# Peripheral.net
KiCad netlist of a schematic drawn in Altium Designer
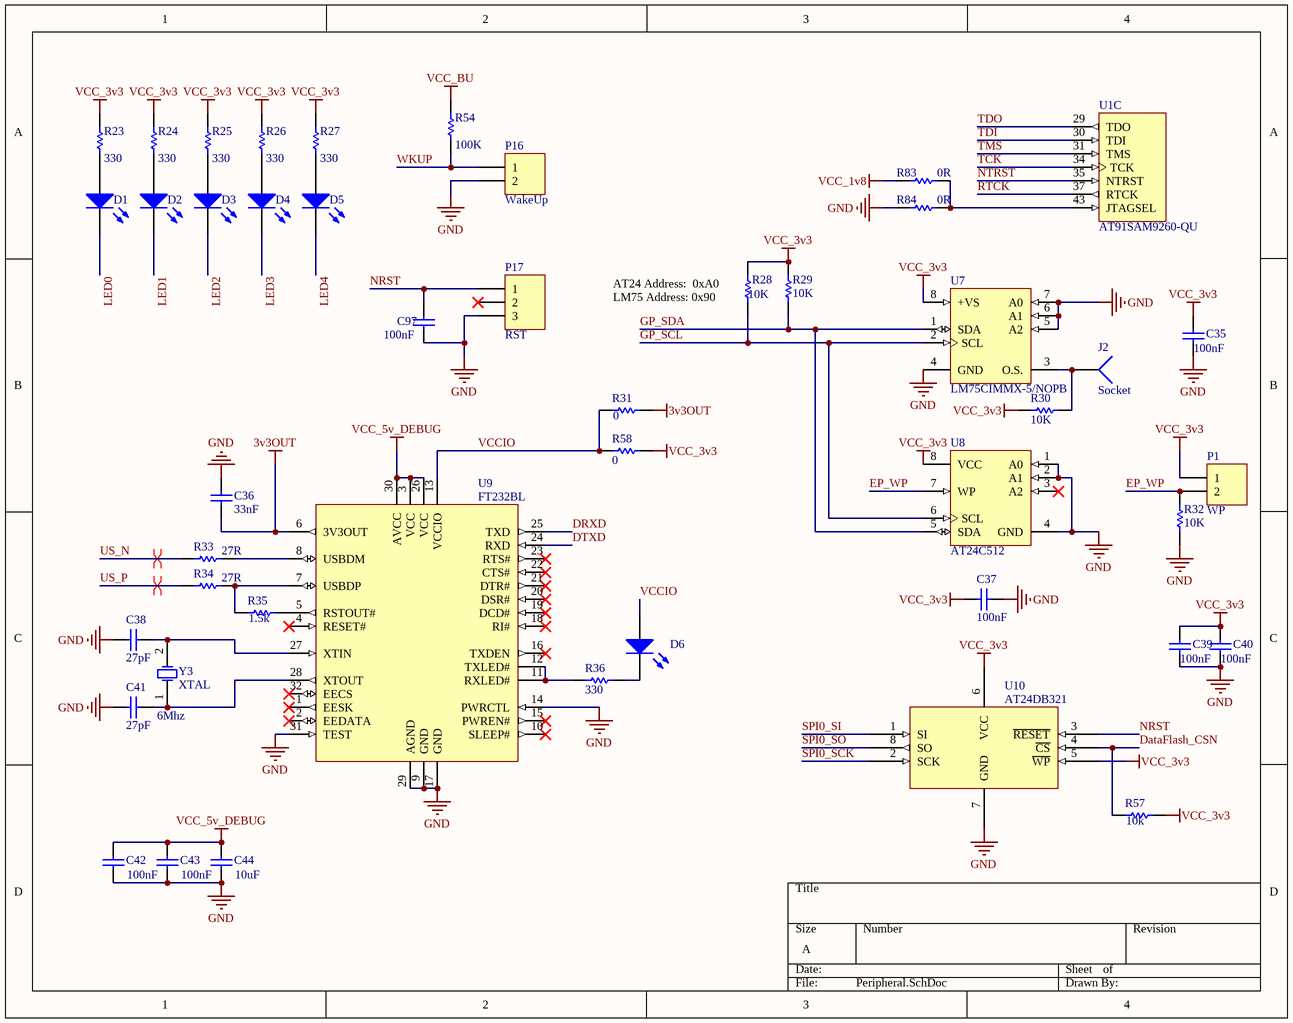
[diagram p0: Peripheral.SchDoc]

(export (version "E")
  (design (tool "Eeschema 10.0.6"))
  (components
    (comp (ref "C35")
      (value "100nF")
      (footprint "C0805")
      (description "Capacitor")
      (fields (field (name "Comment") "Cap") (field (name "PUBLISHER") "Altium Limited"))
      (libsource (lib "Miscellaneous Devices") (part "Cap"))
    )
    (comp (ref "C36")
      (value "33nF")
      (footprint "C0805")
      (description "Capacitor")
      (fields (field (name "Comment") "Cap") (field (name "PUBLISHER") "Altium Limited"))
      (libsource (lib "Miscellaneous Devices") (part "Cap"))
    )
    (comp (ref "C37")
      (value "100nF")
      (footprint "C0805")
      (description "Capacitor")
      (fields (field (name "Comment") "Cap") (field (name "PUBLISHER") "Altium Limited"))
      (libsource (lib "Miscellaneous Devices") (part "Cap"))
    )
    (comp (ref "C38")
      (value "27pF")
      (footprint "C0805")
      (description "Capacitor")
      (fields (field (name "Comment") "Cap") (field (name "PUBLISHER") "Altium Limited"))
      (libsource (lib "Miscellaneous Devices") (part "Cap"))
    )
    (comp (ref "C39")
      (value "100nF")
      (footprint "C0805")
      (description "Capacitor")
      (fields (field (name "Comment") "Cap") (field (name "PUBLISHER") "Altium Limited"))
      (libsource (lib "Miscellaneous Devices") (part "Cap"))
    )
    (comp (ref "C40")
      (value "100nF")
      (footprint "C0805")
      (description "Capacitor")
      (fields (field (name "Comment") "Cap") (field (name "PUBLISHER") "Altium Limited"))
      (libsource (lib "Miscellaneous Devices") (part "Cap"))
    )
    (comp (ref "C41")
      (value "27pF")
      (footprint "C0805")
      (description "Capacitor")
      (fields (field (name "Comment") "Cap") (field (name "PUBLISHER") "Altium Limited"))
      (libsource (lib "Miscellaneous Devices") (part "Cap"))
    )
    (comp (ref "C42")
      (value "100nF")
      (footprint "C0805")
      (description "Capacitor")
      (fields (field (name "Comment") "Cap") (field (name "PUBLISHER") "Altium Limited"))
      (libsource (lib "Miscellaneous Devices") (part "Cap"))
    )
    (comp (ref "C43")
      (value "100nF")
      (footprint "C0805")
      (description "Capacitor")
      (fields (field (name "Comment") "Cap") (field (name "PUBLISHER") "Altium Limited"))
      (libsource (lib "Miscellaneous Devices") (part "Cap"))
    )
    (comp (ref "C44")
      (value "10uF")
      (footprint "C0805")
      (description "Capacitor")
      (fields (field (name "Comment") "Cap") (field (name "PUBLISHER") "Altium Limited"))
      (libsource (lib "Miscellaneous Devices") (part "Cap"))
    )
    (comp (ref "C97")
      (value "100nF")
      (footprint "C0805")
      (description "Capacitor")
      (fields (field (name "Comment") "Cap") (field (name "PUBLISHER") "Altium Limited"))
      (libsource (lib "Miscellaneous Devices") (part "Cap"))
    )
    (comp (ref "D1")
      (value "LED0")
      (footprint "SMD_LED_1206")
      (description "Typical INFRARED GaAs LED")
      (fields (field (name "PUBLISHER") "Altium Limited"))
      (libsource (lib "Miscellaneous Devices") (part "LED0"))
    )
    (comp (ref "D2")
      (value "LED0")
      (footprint "SMD_LED_1206")
      (description "Typical INFRARED GaAs LED")
      (fields (field (name "PUBLISHER") "Altium Limited"))
      (libsource (lib "Miscellaneous Devices") (part "LED0"))
    )
    (comp (ref "D3")
      (value "LED0")
      (footprint "SMD_LED_1206")
      (description "Typical INFRARED GaAs LED")
      (fields (field (name "PUBLISHER") "Altium Limited"))
      (libsource (lib "Miscellaneous Devices") (part "LED0"))
    )
    (comp (ref "D4")
      (value "LED0")
      (footprint "SMD_LED_1206")
      (description "Typical INFRARED GaAs LED")
      (fields (field (name "PUBLISHER") "Altium Limited"))
      (libsource (lib "Miscellaneous Devices") (part "LED0"))
    )
    (comp (ref "D5")
      (value "LED0")
      (footprint "SMD_LED_1206")
      (description "Typical INFRARED GaAs LED")
      (fields (field (name "PUBLISHER") "Altium Limited"))
      (libsource (lib "Miscellaneous Devices") (part "LED0"))
    )
    (comp (ref "D6")
      (value "LED0")
      (footprint "SMD_LED_1206")
      (description "Typical INFRARED GaAs LED")
      (fields (field (name "PUBLISHER") "Altium Limited"))
      (libsource (lib "Miscellaneous Devices") (part "LED0"))
    )
    (comp (ref "J2")
      (value "Socket")
      (footprint "PIN1")
      (fields (field (name "PUBLISHER") "Altium Limited"))
      (libsource (lib "Miscellaneous Connectors") (part "Socket"))
    )
    (comp (ref "P1")
      (value "WP")
      (footprint "HDR1X2")
      (description "Header, 2-Pin")
      (fields (field (name "PUBLISHER") "Altium Limited"))
      (libsource (lib "Miscellaneous Connectors") (part "Header 2"))
    )
    (comp (ref "P16")
      (value "WakeUp")
      (footprint "HDR1X2")
      (description "Header, 2-Pin")
      (fields (field (name "PUBLISHER") "Altium Limited"))
      (libsource (lib "Miscellaneous Connectors") (part "Header 2"))
    )
    (comp (ref "P17")
      (value "RST")
      (footprint "HDR1X3")
      (description "Header, 3-Pin")
      (fields (field (name "PUBLISHER") "Altium Limited"))
      (libsource (lib "Miscellaneous Connectors") (part "Header 3"))
    )
    (comp (ref "R23")
      (value "330")
      (footprint "C0805")
      (description "Semiconductor Resistor")
      (fields (field (name "Comment") "Res Semi") (field (name "PUBLISHER") "Altium Limited"))
      (libsource (lib "Miscellaneous Devices") (part "Res Semi"))
    )
    (comp (ref "R24")
      (value "330")
      (footprint "C0805")
      (description "Semiconductor Resistor")
      (fields (field (name "Comment") "Res Semi") (field (name "PUBLISHER") "Altium Limited"))
      (libsource (lib "Miscellaneous Devices") (part "Res Semi"))
    )
    (comp (ref "R25")
      (value "330")
      (footprint "C0805")
      (description "Semiconductor Resistor")
      (fields (field (name "Comment") "Res Semi") (field (name "PUBLISHER") "Altium Limited"))
      (libsource (lib "Miscellaneous Devices") (part "Res Semi"))
    )
    (comp (ref "R26")
      (value "330")
      (footprint "C0805")
      (description "Semiconductor Resistor")
      (fields (field (name "Comment") "Res Semi") (field (name "PUBLISHER") "Altium Limited"))
      (libsource (lib "Miscellaneous Devices") (part "Res Semi"))
    )
    (comp (ref "R27")
      (value "330")
      (footprint "C0805")
      (description "Semiconductor Resistor")
      (fields (field (name "Comment") "Res Semi") (field (name "PUBLISHER") "Altium Limited"))
      (libsource (lib "Miscellaneous Devices") (part "Res Semi"))
    )
    (comp (ref "R28")
      (value "10K")
      (footprint "C0805")
      (description "Semiconductor Resistor")
      (fields (field (name "Comment") "Res Semi") (field (name "PUBLISHER") "Altium Limited"))
      (libsource (lib "Miscellaneous Devices") (part "Res Semi"))
    )
    (comp (ref "R29")
      (value "10K")
      (footprint "C0805")
      (description "Semiconductor Resistor")
      (fields (field (name "Comment") "Res Semi") (field (name "PUBLISHER") "Altium Limited"))
      (libsource (lib "Miscellaneous Devices") (part "Res Semi"))
    )
    (comp (ref "R30")
      (value "10K")
      (footprint "C0805")
      (description "Semiconductor Resistor")
      (fields (field (name "Comment") "Res Semi") (field (name "PUBLISHER") "Altium Limited"))
      (libsource (lib "Miscellaneous Devices") (part "Res Semi"))
    )
    (comp (ref "R31")
      (value "0")
      (footprint "C0805")
      (description "Semiconductor Resistor")
      (fields (field (name "Comment") "Res Semi") (field (name "PUBLISHER") "Altium Limited"))
      (libsource (lib "Miscellaneous Devices") (part "Res Semi"))
    )
    (comp (ref "R32")
      (value "10K")
      (footprint "C0805")
      (description "Semiconductor Resistor")
      (fields (field (name "Comment") "Res Semi") (field (name "PUBLISHER") "Altium Limited"))
      (libsource (lib "Miscellaneous Devices") (part "Res Semi"))
    )
    (comp (ref "R33")
      (value "27R")
      (footprint "C0805")
      (description "Semiconductor Resistor")
      (fields (field (name "Comment") "Res Semi") (field (name "PUBLISHER") "Altium Limited"))
      (libsource (lib "Miscellaneous Devices") (part "Res Semi"))
    )
    (comp (ref "R34")
      (value "27R")
      (footprint "C0805")
      (description "Semiconductor Resistor")
      (fields (field (name "Comment") "Res Semi") (field (name "PUBLISHER") "Altium Limited"))
      (libsource (lib "Miscellaneous Devices") (part "Res Semi"))
    )
    (comp (ref "R35")
      (value "1.5k")
      (footprint "C0805")
      (description "Semiconductor Resistor")
      (fields (field (name "Comment") "Res Semi") (field (name "PUBLISHER") "Altium Limited"))
      (libsource (lib "Miscellaneous Devices") (part "Res Semi"))
    )
    (comp (ref "R36")
      (value "330")
      (footprint "C0805")
      (description "Semiconductor Resistor")
      (fields (field (name "Comment") "Res Semi") (field (name "PUBLISHER") "Altium Limited"))
      (libsource (lib "Miscellaneous Devices") (part "Res Semi"))
    )
    (comp (ref "R54")
      (value "100K")
      (footprint "C0805")
      (description "Resistor")
      (fields (field (name "Comment") "Res1") (field (name "PUBLISHER") "Altium Limited"))
      (libsource (lib "Miscellaneous Devices") (part "Res1"))
    )
    (comp (ref "R57")
      (value "10k")
      (footprint "C0805")
      (description "Resistor")
      (fields (field (name "Comment") "Res1") (field (name "PUBLISHER") "Altium Limited"))
      (libsource (lib "Miscellaneous Devices") (part "Res1"))
    )
    (comp (ref "R58")
      (value "0")
      (footprint "C0805")
      (description "Semiconductor Resistor")
      (fields (field (name "Comment") "Res Semi") (field (name "PUBLISHER") "Altium Limited"))
      (libsource (lib "Miscellaneous Devices") (part "Res Semi"))
    )
    (comp (ref "R83")
      (value "0R")
      (footprint "0603PKG")
      (description "Semiconductor Resistor")
      (fields (field (name "Comment") "Res Semi") (field (name "PUBLISHER") "Altium Limited"))
      (libsource (lib "Miscellaneous Devices") (part "Res Semi"))
    )
    (comp (ref "R84")
      (value "0R")
      (footprint "0603PKG")
      (description "Semiconductor Resistor")
      (fields (field (name "Comment") "Res Semi") (field (name "PUBLISHER") "Altium Limited"))
      (libsource (lib "Miscellaneous Devices") (part "Res Semi"))
    )
    (comp (ref "U1")
      (value "AT91SAM9260-QU")
      (footprint "SQFP50P3122X3122X245-208N")
      (libsource (lib "Atmel Microcontroller ARM") (part "AT91SAM9260-QU"))
    )
    (comp (ref "U7")
      (value "LM75CIMMX-5/NOPB")
      (footprint "SSOP8")
      (description "Digital Temperature Sensor and Thermal Watchdog with Two-Wire Interface, 8 pin MINI SOIC")
      (fields (field (name "MANUFACTURER") "National Semiconductor"))
      (libsource (lib "National Semiconductor Temperature Sensor") (part "LM75CIMMX-5/NOPB"))
    )
    (comp (ref "U8")
      (value "AT24C512")
      (footprint "SSOP8")
      (description "1Kbit (128 x 8), 2-wire Bus Automotive Serial EEPROM with Write Protect, 2.5V, 8-Pin SOIC, Bulk")
      (libsource (lib "Atmel Serial EEPROM") (part "AT24C01BN-SP25-B"))
    )
    (comp (ref "U9")
      (value "FT232BL")
      (footprint "LQFP-32_N")
      (description "USB UART Asynchronous Serial Data Transfer Chip, 0 to +70 degC, 32-pin LQFP, Pb-Free")
      (fields (field (name "MANUFACTURER") "FTDI"))
      (libsource (lib "FTDI FT Series") (part "FT232BL"))
    )
    (comp (ref "U10")
      (value "AT24DB321")
      (footprint "SSOP8")
      (description "Atmel serial flash")
      (libsource (lib "DE0_IntLib") (part "AT24D321"))
    )
    (comp (ref "Y3")
      (value "XTAL")
      (footprint "SMD_Crystal")
      (description "Crystal Oscillator")
      (fields (field (name "ALTIUM_VALUE") "6Mhz") (field (name "PUBLISHER") "Altium Limited"))
      (libsource (lib "Miscellaneous Devices") (part "XTAL"))
    )
  )
  (nets
    (net (code "1") (name "/DRXD") (class "Default")
      (node (ref "U9") (pin "25") (pinfunction "TXD_25") (pintype "output"))
    )
    (net (code "2") (name "/DTXD") (class "Default")
      (node (ref "U9") (pin "24") (pinfunction "RXD_24") (pintype "input"))
    )
    (net (code "3") (name "/DataFlash_CSN") (class "Default")
      (node (ref "R57") (pin "2") (pinfunction "2_2") (pintype "passive"))
      (node (ref "U10") (pin "4") (pinfunction "~{CS}_4") (pintype "input"))
    )
    (net (code "4") (name "/EP_WP") (class "Default")
      (node (ref "P1") (pin "2") (pinfunction "2_2") (pintype "passive"))
      (node (ref "R32") (pin "2") (pinfunction "2_2") (pintype "passive"))
      (node (ref "U8") (pin "7") (pinfunction "WP_7") (pintype "input"))
    )
    (net (code "5") (name "/GP_SCL") (class "Default")
      (node (ref "R28") (pin "2") (pinfunction "2_2") (pintype "passive"))
      (node (ref "U7") (pin "2") (pinfunction "SCL_2") (pintype "input"))
      (node (ref "U8") (pin "6") (pinfunction "SCL_6") (pintype "input"))
    )
    (net (code "6") (name "/GP_SDA") (class "Default")
      (node (ref "R29") (pin "2") (pinfunction "2_2") (pintype "passive"))
      (node (ref "U7") (pin "1") (pinfunction "SDA_1") (pintype "bidirectional"))
      (node (ref "U8") (pin "5") (pinfunction "SDA_5") (pintype "bidirectional"))
    )
    (net (code "7") (name "/LED0") (class "Default")
      (node (ref "D1") (pin "2") (pinfunction "K_2") (pintype "passive"))
    )
    (net (code "8") (name "/LED1") (class "Default")
      (node (ref "D2") (pin "2") (pinfunction "K_2") (pintype "passive"))
    )
    (net (code "9") (name "/LED2") (class "Default")
      (node (ref "D3") (pin "2") (pinfunction "K_2") (pintype "passive"))
    )
    (net (code "10") (name "/LED3") (class "Default")
      (node (ref "D4") (pin "2") (pinfunction "K_2") (pintype "passive"))
    )
    (net (code "11") (name "/LED4") (class "Default")
      (node (ref "D5") (pin "2") (pinfunction "K_2") (pintype "passive"))
    )
    (net (code "12") (name "/NRST") (class "Default")
      (node (ref "C97") (pin "2") (pinfunction "2_2") (pintype "passive"))
      (node (ref "P17") (pin "1") (pinfunction "1_1") (pintype "passive"))
      (node (ref "U10") (pin "3") (pinfunction "~{RESET}_3") (pintype "input"))
    )
    (net (code "13") (name "/NTRST") (class "Default")
      (node (ref "U1") (pin "35") (pinfunction "NTRST_35") (pintype "input"))
    )
    (net (code "14") (name "/RTCK") (class "Default")
      (node (ref "U1") (pin "37") (pinfunction "RTCK_37") (pintype "output"))
    )
    (net (code "15") (name "/SPI0_SCK") (class "Default")
      (node (ref "U10") (pin "2") (pinfunction "SCK_2") (pintype "input"))
    )
    (net (code "16") (name "/SPI0_SI") (class "Default")
      (node (ref "U10") (pin "1") (pinfunction "SI_1") (pintype "input"))
    )
    (net (code "17") (name "/SPI0_SO") (class "Default")
      (node (ref "U10") (pin "8") (pinfunction "SO_8") (pintype "output"))
    )
    (net (code "18") (name "/TCK") (class "Default")
      (node (ref "U1") (pin "34") (pinfunction "TCK_34") (pintype "input"))
    )
    (net (code "19") (name "/TDI") (class "Default")
      (node (ref "U1") (pin "30") (pinfunction "TDI_30") (pintype "input"))
    )
    (net (code "20") (name "/TDO") (class "Default")
      (node (ref "U1") (pin "29") (pinfunction "TDO_29") (pintype "output"))
    )
    (net (code "21") (name "/TMS") (class "Default")
      (node (ref "U1") (pin "31") (pinfunction "TMS_31") (pintype "input"))
    )
    (net (code "22") (name "/US_N") (class "Default")
      (node (ref "R33") (pin "2") (pinfunction "2_2") (pintype "passive"))
    )
    (net (code "23") (name "/US_P") (class "Default")
      (node (ref "R34") (pin "2") (pinfunction "2_2") (pintype "passive"))
    )
    (net (code "24") (name "/VCCIO") (class "Default")
      (node (ref "D6") (pin "1") (pinfunction "A_1") (pintype "passive"))
      (node (ref "R31") (pin "1") (pinfunction "1_1") (pintype "passive"))
      (node (ref "R58") (pin "1") (pinfunction "1_1") (pintype "passive"))
      (node (ref "U9") (pin "13") (pinfunction "VCCIO_13") (pintype "power_in"))
    )
    (net (code "25") (name "/WKUP") (class "Default")
      (node (ref "P16") (pin "1") (pinfunction "1_1") (pintype "passive"))
      (node (ref "R54") (pin "1") (pinfunction "1_1") (pintype "passive"))
    )
    (net (code "26") (name "3v3OUT") (class "Default")
      (node (ref "C36") (pin "2") (pinfunction "2_2") (pintype "passive"))
      (node (ref "R31") (pin "2") (pinfunction "2_2") (pintype "passive"))
      (node (ref "U9") (pin "6") (pinfunction "3V3OUT_6") (pintype "output"))
    )
    (net (code "27") (name "GND") (class "Default")
      (node (ref "C35") (pin "1") (pinfunction "1_1") (pintype "passive"))
      (node (ref "C36") (pin "1") (pinfunction "1_1") (pintype "passive"))
      (node (ref "C37") (pin "1") (pinfunction "1_1") (pintype "passive"))
      (node (ref "C38") (pin "2") (pinfunction "2_2") (pintype "passive"))
      (node (ref "C39") (pin "1") (pinfunction "1_1") (pintype "passive"))
      (node (ref "C40") (pin "1") (pinfunction "1_1") (pintype "passive"))
      (node (ref "C41") (pin "2") (pinfunction "2_2") (pintype "passive"))
      (node (ref "C42") (pin "1") (pinfunction "1_1") (pintype "passive"))
      (node (ref "C43") (pin "1") (pinfunction "1_1") (pintype "passive"))
      (node (ref "C44") (pin "1") (pinfunction "1_1") (pintype "passive"))
      (node (ref "C97") (pin "1") (pinfunction "1_1") (pintype "passive"))
      (node (ref "P16") (pin "2") (pinfunction "2_2") (pintype "passive"))
      (node (ref "P17") (pin "3") (pinfunction "3_3") (pintype "passive"))
      (node (ref "R32") (pin "1") (pinfunction "1_1") (pintype "passive"))
      (node (ref "R84") (pin "2") (pinfunction "2_2") (pintype "passive"))
      (node (ref "U10") (pin "7") (pinfunction "GND_7") (pintype "power_in"))
      (node (ref "U7") (pin "4") (pinfunction "GND_4") (pintype "power_in"))
      (node (ref "U7") (pin "5") (pinfunction "A2_5") (pintype "input"))
      (node (ref "U7") (pin "6") (pinfunction "A1_6") (pintype "input"))
      (node (ref "U7") (pin "7") (pinfunction "A0_7") (pintype "input"))
      (node (ref "U8") (pin "1") (pinfunction "A0_1") (pintype "input"))
      (node (ref "U8") (pin "2") (pinfunction "A1_2") (pintype "input"))
      (node (ref "U8") (pin "4") (pinfunction "GND_4") (pintype "power_in"))
      (node (ref "U9") (pin "14") (pinfunction "PWRCTL_14") (pintype "input"))
      (node (ref "U9") (pin "17") (pinfunction "GND_17") (pintype "power_in"))
      (node (ref "U9") (pin "29") (pinfunction "AGND_29") (pintype "power_in"))
      (node (ref "U9") (pin "31") (pinfunction "TEST_31") (pintype "input"))
      (node (ref "U9") (pin "9") (pinfunction "GND_9") (pintype "power_in"))
    )
    (net (code "28") (name "Net-(D1-A)") (class "Default")
      (node (ref "D1") (pin "1") (pinfunction "A_1") (pintype "passive"))
      (node (ref "R23") (pin "1") (pinfunction "1_1") (pintype "passive"))
    )
    (net (code "29") (name "Net-(D2-A)") (class "Default")
      (node (ref "D2") (pin "1") (pinfunction "A_1") (pintype "passive"))
      (node (ref "R24") (pin "1") (pinfunction "1_1") (pintype "passive"))
    )
    (net (code "30") (name "Net-(D3-A)") (class "Default")
      (node (ref "D3") (pin "1") (pinfunction "A_1") (pintype "passive"))
      (node (ref "R25") (pin "1") (pinfunction "1_1") (pintype "passive"))
    )
    (net (code "31") (name "Net-(D4-A)") (class "Default")
      (node (ref "D4") (pin "1") (pinfunction "A_1") (pintype "passive"))
      (node (ref "R26") (pin "1") (pinfunction "1_1") (pintype "passive"))
    )
    (net (code "32") (name "Net-(D5-A)") (class "Default")
      (node (ref "D5") (pin "1") (pinfunction "A_1") (pintype "passive"))
      (node (ref "R27") (pin "1") (pinfunction "1_1") (pintype "passive"))
    )
    (net (code "33") (name "Net-(D6-K)") (class "Default")
      (node (ref "D6") (pin "2") (pinfunction "K_2") (pintype "passive"))
      (node (ref "R36") (pin "1") (pinfunction "1_1") (pintype "passive"))
    )
    (net (code "34") (name "Net-(U1C-JTAGSEL)") (class "Default")
      (node (ref "R83") (pin "1") (pinfunction "1_1") (pintype "passive"))
      (node (ref "R84") (pin "1") (pinfunction "1_1") (pintype "passive"))
      (node (ref "U1") (pin "43") (pinfunction "JTAGSEL_43") (pintype "input"))
    )
    (net (code "35") (name "Net-(U7-O.S.)") (class "Default")
      (node (ref "J2") (pin "1") (pinfunction "1_1") (pintype "passive"))
      (node (ref "R30") (pin "2") (pinfunction "2_2") (pintype "passive"))
      (node (ref "U7") (pin "3") (pinfunction "O.S._3") (pintype "open_collector"))
    )
    (net (code "36") (name "Net-(U9-RSTOUT#)") (class "Default")
      (node (ref "R35") (pin "1") (pinfunction "1_1") (pintype "passive"))
      (node (ref "U9") (pin "5") (pinfunction "RSTOUT#_5") (pintype "output"))
    )
    (net (code "37") (name "Net-(U9-RXLED#)") (class "Default")
      (node (ref "R36") (pin "2") (pinfunction "2_2") (pintype "passive"))
      (node (ref "U9") (pin "11") (pinfunction "RXLED#_11") (pintype "open_collector"))
      (node (ref "U9") (pin "12") (pinfunction "TXLED#_12") (pintype "open_collector"))
    )
    (net (code "38") (name "Net-(U9-USBDM)") (class "Default")
      (node (ref "R33") (pin "1") (pinfunction "1_1") (pintype "passive"))
      (node (ref "U9") (pin "8") (pinfunction "USBDM_8") (pintype "bidirectional"))
    )
    (net (code "39") (name "Net-(U9-USBDP)") (class "Default")
      (node (ref "R34") (pin "1") (pinfunction "1_1") (pintype "passive"))
      (node (ref "R35") (pin "2") (pinfunction "2_2") (pintype "passive"))
      (node (ref "U9") (pin "7") (pinfunction "USBDP_7") (pintype "bidirectional"))
    )
    (net (code "40") (name "Net-(U9-XTIN)") (class "Default")
      (node (ref "C38") (pin "1") (pinfunction "1_1") (pintype "passive"))
      (node (ref "U9") (pin "27") (pinfunction "XTIN_27") (pintype "input"))
      (node (ref "Y3") (pin "2") (pinfunction "OSC2_2") (pintype "passive"))
    )
    (net (code "41") (name "Net-(U9-XTOUT)") (class "Default")
      (node (ref "C41") (pin "1") (pinfunction "1_1") (pintype "passive"))
      (node (ref "U9") (pin "28") (pinfunction "XTOUT_28") (pintype "output"))
      (node (ref "Y3") (pin "1") (pinfunction "OSC1_1") (pintype "passive"))
    )
    (net (code "42") (name "VCC_1v8") (class "Default")
      (node (ref "R83") (pin "2") (pinfunction "2_2") (pintype "passive"))
    )
    (net (code "43") (name "VCC_3v3") (class "Default")
      (node (ref "C35") (pin "2") (pinfunction "2_2") (pintype "passive"))
      (node (ref "C37") (pin "2") (pinfunction "2_2") (pintype "passive"))
      (node (ref "C39") (pin "2") (pinfunction "2_2") (pintype "passive"))
      (node (ref "C40") (pin "2") (pinfunction "2_2") (pintype "passive"))
      (node (ref "P1") (pin "1") (pinfunction "1_1") (pintype "passive"))
      (node (ref "R23") (pin "2") (pinfunction "2_2") (pintype "passive"))
      (node (ref "R24") (pin "2") (pinfunction "2_2") (pintype "passive"))
      (node (ref "R25") (pin "2") (pinfunction "2_2") (pintype "passive"))
      (node (ref "R26") (pin "2") (pinfunction "2_2") (pintype "passive"))
      (node (ref "R27") (pin "2") (pinfunction "2_2") (pintype "passive"))
      (node (ref "R28") (pin "1") (pinfunction "1_1") (pintype "passive"))
      (node (ref "R29") (pin "1") (pinfunction "1_1") (pintype "passive"))
      (node (ref "R30") (pin "1") (pinfunction "1_1") (pintype "passive"))
      (node (ref "R57") (pin "1") (pinfunction "1_1") (pintype "passive"))
      (node (ref "R58") (pin "2") (pinfunction "2_2") (pintype "passive"))
      (node (ref "U10") (pin "5") (pinfunction "~{WP}_5") (pintype "input"))
      (node (ref "U10") (pin "6") (pinfunction "VCC_6") (pintype "power_in"))
      (node (ref "U7") (pin "8") (pinfunction "+VS_8") (pintype "input"))
      (node (ref "U8") (pin "8") (pinfunction "VCC_8") (pintype "power_in"))
    )
    (net (code "44") (name "VCC_5v_DEBUG") (class "Default")
      (node (ref "C42") (pin "2") (pinfunction "2_2") (pintype "passive"))
      (node (ref "C43") (pin "2") (pinfunction "2_2") (pintype "passive"))
      (node (ref "C44") (pin "2") (pinfunction "2_2") (pintype "passive"))
      (node (ref "U9") (pin "26") (pinfunction "VCC_26") (pintype "power_in"))
      (node (ref "U9") (pin "3") (pinfunction "VCC_3") (pintype "power_in"))
      (node (ref "U9") (pin "30") (pinfunction "AVCC_30") (pintype "power_in"))
    )
    (net (code "45") (name "VCC_BU") (class "Default")
      (node (ref "R54") (pin "2") (pinfunction "2_2") (pintype "passive"))
    )
    (net (code "46") (name "unconnected-(P17-Pad2)") (class "Default")
      (node (ref "P17") (pin "2") (pinfunction "2_2") (pintype "passive+no_connect"))
    )
    (net (code "47") (name "unconnected-(U8-A2-Pad3)") (class "Default")
      (node (ref "U8") (pin "3") (pinfunction "A2_3") (pintype "input+no_connect"))
    )
    (net (code "48") (name "unconnected-(U9-CTS#-Pad22)") (class "Default")
      (node (ref "U9") (pin "22") (pinfunction "CTS#_22") (pintype "input+no_connect"))
    )
    (net (code "49") (name "unconnected-(U9-DCD#-Pad19)") (class "Default")
      (node (ref "U9") (pin "19") (pinfunction "DCD#_19") (pintype "input+no_connect"))
    )
    (net (code "50") (name "unconnected-(U9-DSR#-Pad20)") (class "Default")
      (node (ref "U9") (pin "20") (pinfunction "DSR#_20") (pintype "input+no_connect"))
    )
    (net (code "51") (name "unconnected-(U9-DTR#-Pad21)") (class "Default")
      (node (ref "U9") (pin "21") (pinfunction "DTR#_21") (pintype "output+no_connect"))
    )
    (net (code "52") (name "unconnected-(U9-EECS-Pad32)") (class "Default")
      (node (ref "U9") (pin "32") (pinfunction "EECS_32") (pintype "bidirectional+no_connect"))
    )
    (net (code "53") (name "unconnected-(U9-EEDATA-Pad2)") (class "Default")
      (node (ref "U9") (pin "2") (pinfunction "EEDATA_2") (pintype "bidirectional+no_connect"))
    )
    (net (code "54") (name "unconnected-(U9-EESK-Pad1)") (class "Default")
      (node (ref "U9") (pin "1") (pinfunction "EESK_1") (pintype "output+no_connect"))
    )
    (net (code "55") (name "unconnected-(U9-PWREN#-Pad15)") (class "Default")
      (node (ref "U9") (pin "15") (pinfunction "PWREN#_15") (pintype "output+no_connect"))
    )
    (net (code "56") (name "unconnected-(U9-RESET#-Pad4)") (class "Default")
      (node (ref "U9") (pin "4") (pinfunction "RESET#_4") (pintype "input+no_connect"))
    )
    (net (code "57") (name "unconnected-(U9-RI#-Pad18)") (class "Default")
      (node (ref "U9") (pin "18") (pinfunction "RI#_18") (pintype "input+no_connect"))
    )
    (net (code "58") (name "unconnected-(U9-RTS#-Pad23)") (class "Default")
      (node (ref "U9") (pin "23") (pinfunction "RTS#_23") (pintype "output+no_connect"))
    )
    (net (code "59") (name "unconnected-(U9-SLEEP#-Pad10)") (class "Default")
      (node (ref "U9") (pin "10") (pinfunction "SLEEP#_10") (pintype "output+no_connect"))
    )
    (net (code "60") (name "unconnected-(U9-TXDEN-Pad16)") (class "Default")
      (node (ref "U9") (pin "16") (pinfunction "TXDEN_16") (pintype "output+no_connect"))
    )
  )
)
